# Lab7-8_TOP.net
KiCad netlist of a schematic drawn in Altium Designer
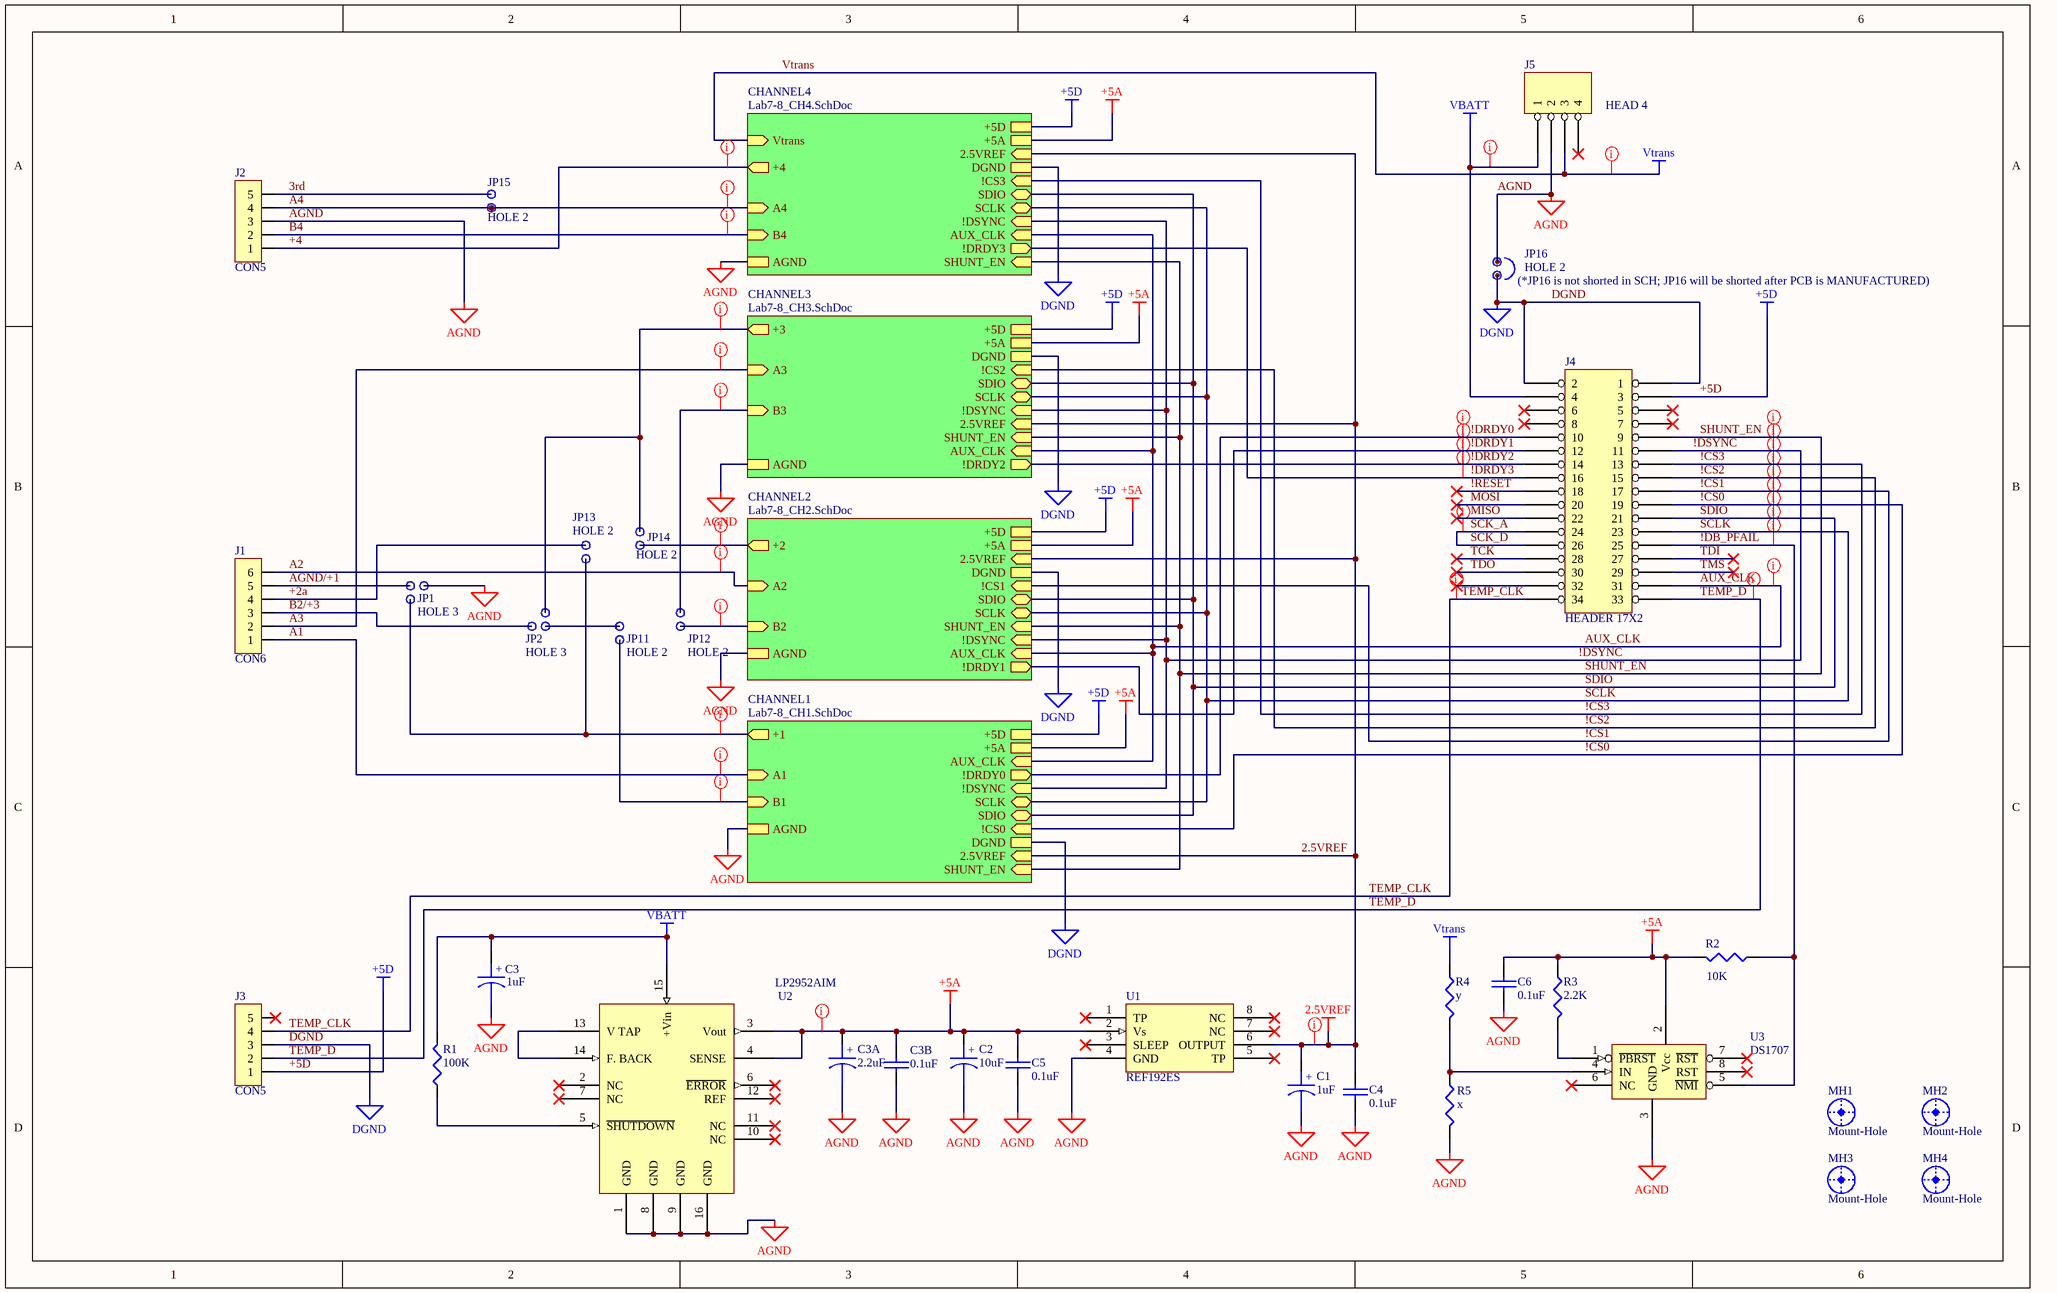
[diagram p0: Lab7-8_TOP.SchDoc]

(export (version "E")
  (design (tool "Eeschema 10.0.6"))
  (components
    (comp (ref "C1")
      (value "1uF")
      (footprint "3528")
      (libsource (lib "ECET231_ProjectThree_SCHLIB_Rev02") (part "CAPACITOR POL"))
    )
    (comp (ref "C2")
      (value "10uF")
      (footprint "3528")
      (libsource (lib "ECET231_ProjectThree_SCHLIB_Rev02") (part "CAPACITOR POL"))
    )
    (comp (ref "C3")
      (value "1uF")
      (footprint "3528")
      (libsource (lib "ECET231_ProjectThree_SCHLIB_Rev02") (part "CAPACITOR POL"))
    )
    (comp (ref "C3A")
      (value "2.2uF")
      (footprint "3528")
      (libsource (lib "ECET231_ProjectThree_SCHLIB_Rev02") (part "CAPACITOR POL"))
    )
    (comp (ref "C3B")
      (value "0.1uF")
      (footprint "0805")
      (libsource (lib "ECET231_ProjectThree_SCHLIB_Rev02") (part "CAP"))
    )
    (comp (ref "C4")
      (value "0.1uF")
      (footprint "0805")
      (libsource (lib "ECET231_ProjectThree_SCHLIB_Rev02") (part "CAP"))
    )
    (comp (ref "C5")
      (value "0.1uF")
      (footprint "0805")
      (libsource (lib "ECET231_ProjectThree_SCHLIB_Rev02") (part "CAP"))
    )
    (comp (ref "C6")
      (value "0.1uF")
      (footprint "0805")
      (libsource (lib "ECET231_ProjectThree_SCHLIB_Rev02") (part "CAP"))
    )
    (comp (ref "J1")
      (value "CON6")
      (footprint "FSFD4.6")
      (libsource (lib "ECET231_ProjectThree_SCHLIB_Rev02") (part "CON6"))
    )
    (comp (ref "J2")
      (value "CON5")
      (footprint "FSFD4.5")
      (libsource (lib "ECET231_ProjectThree_SCHLIB_Rev02") (part "CON5"))
    )
    (comp (ref "J3")
      (value "CON5")
      (footprint "FSFD4.5")
      (libsource (lib "ECET231_ProjectThree_SCHLIB_Rev02") (part "CON5"))
    )
    (comp (ref "J4")
      (value "HEADER 17X2")
      (footprint "HDR2X17")
      (libsource (lib "ECET231_ProjectThree_SCHLIB_Rev02") (part "HEADER 2X17"))
    )
    (comp (ref "J5")
      (value "HEAD 4")
      (footprint "70543-4A")
      (libsource (lib "ECET231_ProjectThree_SCHLIB_Rev02") (part "HEADER 4"))
    )
    (comp (ref "JP1")
      (value "HOLE 3")
      (footprint "RAD0.1A")
      (libsource (lib "ECET231_ProjectThree_SCHLIB_Rev02") (part "HOLE 3"))
    )
    (comp (ref "JP2")
      (value "HOLE 3")
      (footprint "RAD0.1A")
      (libsource (lib "ECET231_ProjectThree_SCHLIB_Rev02") (part "HOLE 3"))
    )
    (comp (ref "JP11")
      (value "HOLE 2")
      (footprint "RAD0.1")
      (libsource (lib "ECET231_ProjectThree_SCHLIB_Rev02") (part "HOLE 2"))
    )
    (comp (ref "JP12")
      (value "HOLE 2")
      (footprint "RAD0.1")
      (libsource (lib "ECET231_ProjectThree_SCHLIB_Rev02") (part "HOLE 2"))
    )
    (comp (ref "JP13")
      (value "HOLE 2")
      (footprint "RAD0.1")
      (libsource (lib "ECET231_ProjectThree_SCHLIB_Rev02") (part "HOLE 2"))
    )
    (comp (ref "JP14")
      (value "HOLE 2")
      (footprint "RAD0.1")
      (libsource (lib "ECET231_ProjectThree_SCHLIB_Rev02") (part "HOLE 2"))
    )
    (comp (ref "JP15")
      (value "HOLE 2")
      (footprint "RAD0.1")
      (libsource (lib "ECET231_ProjectThree_SCHLIB_Rev02") (part "HOLE 2"))
    )
    (comp (ref "JP16")
      (value "HOLE 2")
      (footprint "RAD0.1")
      (libsource (lib "ECET231_ProjectThree_SCHLIB_Rev02") (part "HOLE 2"))
    )
    (comp (ref "MH1")
      (value "Mount-Hole")
      (footprint "screw 4-40")
      (description "Mount hole")
      (fields (field (name "PUBLISHER") "Altium Limited"))
      (libsource (lib "ECET231_ProjectThree_SCHLIB_Rev02") (part "MountHole"))
    )
    (comp (ref "MH2")
      (value "Mount-Hole")
      (footprint "screw 4-40")
      (description "Mount hole")
      (fields (field (name "PUBLISHER") "Altium Limited"))
      (libsource (lib "ECET231_ProjectThree_SCHLIB_Rev02") (part "MountHole"))
    )
    (comp (ref "MH3")
      (value "Mount-Hole")
      (footprint "screw 4-40")
      (description "Mount hole")
      (fields (field (name "PUBLISHER") "Altium Limited"))
      (libsource (lib "ECET231_ProjectThree_SCHLIB_Rev02") (part "MountHole"))
    )
    (comp (ref "MH4")
      (value "Mount-Hole")
      (footprint "screw 4-40")
      (description "Mount hole")
      (fields (field (name "PUBLISHER") "Altium Limited"))
      (libsource (lib "ECET231_ProjectThree_SCHLIB_Rev02") (part "MountHole"))
    )
    (comp (ref "R1")
      (value "100K")
      (footprint "0805")
      (libsource (lib "ECET231_ProjectThree_SCHLIB_Rev02") (part "RES1"))
    )
    (comp (ref "R2")
      (value "10K")
      (footprint "0805")
      (libsource (lib "ECET231_ProjectThree_SCHLIB_Rev02") (part "RES1"))
    )
    (comp (ref "R3")
      (value "2.2K")
      (footprint "0805")
      (libsource (lib "ECET231_ProjectThree_SCHLIB_Rev02") (part "RES1"))
    )
    (comp (ref "R4")
      (value "y")
      (footprint "0805")
      (libsource (lib "ECET231_ProjectThree_SCHLIB_Rev02") (part "RES1"))
    )
    (comp (ref "R5")
      (value "x")
      (footprint "0805")
      (libsource (lib "ECET231_ProjectThree_SCHLIB_Rev02") (part "RES1"))
    )
    (comp (ref "U1")
      (value "REF192ES")
      (footprint "SO-8")
      (libsource (lib "ECET231_ProjectThree_SCHLIB_Rev02") (part "REF192ES"))
    )
    (comp (ref "U2")
      (value "LP2952AIM")
      (footprint "SO-16")
      (libsource (lib "ECET231_ProjectThree_SCHLIB_Rev02") (part "LP2952AIM"))
    )
    (comp (ref "U3")
      (value "DS1707")
      (footprint "SO-8")
      (libsource (lib "ECET231_ProjectThree_SCHLIB_Rev02") (part "DS1707"))
    )
  )
  (nets
    (net (code "1") (name "+5A") (class "Default")
      (node (ref "C2") (pin "1") (pinfunction "1_1") (pintype "passive"))
      (node (ref "C3A") (pin "1") (pinfunction "1_1") (pintype "passive"))
      (node (ref "C3B") (pin "1") (pintype "passive"))
      (node (ref "C5") (pin "1") (pintype "passive"))
      (node (ref "C6") (pin "1") (pintype "passive"))
      (node (ref "R2") (pin "2") (pintype "passive"))
      (node (ref "R3") (pin "1") (pintype "passive"))
      (node (ref "U1") (pin "2") (pinfunction "Vs_2") (pintype "input"))
      (node (ref "U2") (pin "3") (pinfunction "Vout_3") (pintype "output"))
      (node (ref "U2") (pin "4") (pinfunction "SENSE_4") (pintype "passive"))
      (node (ref "U3") (pin "2") (pinfunction "Vcc_2") (pintype "power_in"))
    )
    (net (code "2") (name "+5D") (class "Default")
      (node (ref "J3") (pin "1") (pinfunction "1_1") (pintype "passive"))
      (node (ref "J4") (pin "3") (pinfunction "3_3") (pintype "passive"))
    )
    (net (code "3") (name "/!CS0") (class "Default")
      (node (ref "J4") (pin "19") (pinfunction "19_19") (pintype "passive"))
    )
    (net (code "4") (name "/!CS1") (class "Default")
      (node (ref "J4") (pin "17") (pinfunction "17_17") (pintype "passive"))
    )
    (net (code "5") (name "/!CS2") (class "Default")
      (node (ref "J4") (pin "15") (pinfunction "15_15") (pintype "passive"))
    )
    (net (code "6") (name "/!CS3") (class "Default")
      (node (ref "J4") (pin "13") (pinfunction "13_13") (pintype "passive"))
    )
    (net (code "7") (name "/!DB_PFAIL") (class "Default")
      (node (ref "J4") (pin "25") (pinfunction "25_25") (pintype "passive"))
      (node (ref "R2") (pin "1") (pintype "passive"))
      (node (ref "U3") (pin "5") (pinfunction "~{NMI}_5") (pintype "passive"))
    )
    (net (code "8") (name "/!DRDY0") (class "Default")
      (node (ref "J4") (pin "10") (pinfunction "10_10") (pintype "passive"))
    )
    (net (code "9") (name "/!DRDY1") (class "Default")
      (node (ref "J4") (pin "12") (pinfunction "12_12") (pintype "passive"))
    )
    (net (code "10") (name "/!DRDY2") (class "Default")
      (node (ref "J4") (pin "14") (pinfunction "14_14") (pintype "passive"))
    )
    (net (code "11") (name "/!DRDY3") (class "Default")
      (node (ref "J4") (pin "16") (pinfunction "16_16") (pintype "passive"))
    )
    (net (code "12") (name "/!DSYNC") (class "Default")
      (node (ref "J4") (pin "11") (pinfunction "11_11") (pintype "passive"))
    )
    (net (code "13") (name "/!RESET") (class "Default")
      (node (ref "J4") (pin "18") (pinfunction "18_18") (pintype "passive+no_connect"))
    )
    (net (code "14") (name "/+1") (class "Default")
      (node (ref "JP1") (pin "1") (pinfunction "1_1") (pintype "passive"))
      (node (ref "JP13") (pin "1") (pinfunction "1_1") (pintype "passive"))
    )
    (net (code "15") (name "/+2") (class "Default")
      (node (ref "JP14") (pin "1") (pinfunction "1_1") (pintype "passive"))
    )
    (net (code "16") (name "/+2a") (class "Default")
      (node (ref "J1") (pin "4") (pinfunction "4_4") (pintype "passive"))
      (node (ref "JP13") (pin "2") (pinfunction "2_2") (pintype "passive"))
    )
    (net (code "17") (name "/+3") (class "Default")
      (node (ref "JP14") (pin "2") (pinfunction "2_2") (pintype "passive"))
      (node (ref "JP2") (pin "1") (pinfunction "1_1") (pintype "passive"))
    )
    (net (code "18") (name "/+4") (class "Default")
      (node (ref "J2") (pin "1") (pinfunction "1_1") (pintype "passive"))
    )
    (net (code "19") (name "/3rd") (class "Default")
      (node (ref "J2") (pin "5") (pinfunction "5_5") (pintype "passive"))
      (node (ref "JP15") (pin "2") (pinfunction "2_2") (pintype "passive"))
    )
    (net (code "20") (name "/A1") (class "Default")
      (node (ref "J1") (pin "1") (pinfunction "1_1") (pintype "passive"))
    )
    (net (code "21") (name "/A2") (class "Default")
      (node (ref "J1") (pin "6") (pinfunction "6_6") (pintype "passive"))
    )
    (net (code "22") (name "/A3") (class "Default")
      (node (ref "J1") (pin "2") (pinfunction "2_2") (pintype "passive"))
    )
    (net (code "23") (name "/A4") (class "Default")
      (node (ref "J2") (pin "4") (pinfunction "4_4") (pintype "passive"))
      (node (ref "JP15") (pin "1") (pinfunction "1_1") (pintype "passive"))
    )
    (net (code "24") (name "/AGND{slash}+1") (class "Default")
      (node (ref "J1") (pin "5") (pinfunction "5_5") (pintype "passive"))
      (node (ref "JP1") (pin "2") (pinfunction "2_2") (pintype "passive"))
    )
    (net (code "25") (name "/AUX_CLK") (class "Default")
      (node (ref "J4") (pin "31") (pinfunction "31_31") (pintype "passive"))
    )
    (net (code "26") (name "/B1") (class "Default")
      (node (ref "JP11") (pin "1") (pinfunction "1_1") (pintype "passive"))
    )
    (net (code "27") (name "/B2") (class "Default")
      (node (ref "JP12") (pin "1") (pinfunction "1_1") (pintype "passive"))
    )
    (net (code "28") (name "/B2{slash}+3") (class "Default")
      (node (ref "J1") (pin "3") (pinfunction "3_3") (pintype "passive"))
      (node (ref "JP2") (pin "3") (pinfunction "3_3") (pintype "passive"))
    )
    (net (code "29") (name "/B3") (class "Default")
      (node (ref "JP12") (pin "2") (pinfunction "2_2") (pintype "passive"))
    )
    (net (code "30") (name "/B4") (class "Default")
      (node (ref "J2") (pin "2") (pinfunction "2_2") (pintype "passive"))
    )
    (net (code "31") (name "/MISO") (class "Default")
      (node (ref "J4") (pin "22") (pinfunction "22_22") (pintype "passive+no_connect"))
    )
    (net (code "32") (name "/MOSI") (class "Default")
      (node (ref "J4") (pin "20") (pinfunction "20_20") (pintype "passive+no_connect"))
    )
    (net (code "33") (name "/SCK_A") (class "Default")
      (node (ref "J4") (pin "24") (pinfunction "24_24") (pintype "passive"))
      (node (ref "J4") (pin "26") (pinfunction "26_26") (pintype "passive"))
    )
    (net (code "34") (name "/SCLK") (class "Default")
      (node (ref "J4") (pin "23") (pinfunction "23_23") (pintype "passive"))
    )
    (net (code "35") (name "/SDIO") (class "Default")
      (node (ref "J4") (pin "21") (pinfunction "21_21") (pintype "passive"))
    )
    (net (code "36") (name "/SHUNT_EN") (class "Default")
      (node (ref "J4") (pin "9") (pinfunction "9_9") (pintype "passive"))
    )
    (net (code "37") (name "/TCK") (class "Default")
      (node (ref "J4") (pin "28") (pinfunction "28_28") (pintype "passive+no_connect"))
    )
    (net (code "38") (name "/TDI") (class "Default")
      (node (ref "J4") (pin "27") (pinfunction "27_27") (pintype "passive+no_connect"))
    )
    (net (code "39") (name "/TDO") (class "Default")
      (node (ref "J4") (pin "30") (pinfunction "30_30") (pintype "passive+no_connect"))
    )
    (net (code "40") (name "/TEMP_CLK") (class "Default")
      (node (ref "J3") (pin "4") (pinfunction "4_4") (pintype "passive"))
      (node (ref "J4") (pin "34") (pinfunction "34_34") (pintype "passive"))
    )
    (net (code "41") (name "/TEMP_D") (class "Default")
      (node (ref "J3") (pin "2") (pinfunction "2_2") (pintype "passive"))
      (node (ref "J4") (pin "33") (pinfunction "33_33") (pintype "passive"))
    )
    (net (code "42") (name "/TMS") (class "Default")
      (node (ref "J4") (pin "29") (pinfunction "29_29") (pintype "passive+no_connect"))
    )
    (net (code "43") (name "2.5VREF") (class "Default")
      (node (ref "C1") (pin "1") (pinfunction "1_1") (pintype "passive"))
      (node (ref "C4") (pin "1") (pintype "passive"))
      (node (ref "U1") (pin "6") (pinfunction "OUTPUT_6") (pintype "passive"))
    )
    (net (code "44") (name "AGND") (class "Default")
      (node (ref "C1") (pin "2") (pinfunction "2_2") (pintype "passive"))
      (node (ref "C2") (pin "2") (pinfunction "2_2") (pintype "passive"))
      (node (ref "C3") (pin "2") (pinfunction "2_2") (pintype "passive"))
      (node (ref "C3A") (pin "2") (pinfunction "2_2") (pintype "passive"))
      (node (ref "C3B") (pin "2") (pintype "passive"))
      (node (ref "C4") (pin "2") (pintype "passive"))
      (node (ref "C5") (pin "2") (pintype "passive"))
      (node (ref "C6") (pin "2") (pintype "passive"))
      (node (ref "J2") (pin "3") (pinfunction "3_3") (pintype "passive"))
      (node (ref "J5") (pin "2") (pinfunction "2_2") (pintype "passive"))
      (node (ref "JP1") (pin "3") (pinfunction "3_3") (pintype "passive"))
      (node (ref "JP16") (pin "2") (pinfunction "2_2") (pintype "passive"))
      (node (ref "R5") (pin "2") (pintype "passive"))
      (node (ref "U1") (pin "4") (pinfunction "GND_4") (pintype "passive"))
      (node (ref "U2") (pin "1") (pinfunction "GND_1") (pintype "passive"))
      (node (ref "U2") (pin "16") (pinfunction "GND_16") (pintype "passive"))
      (node (ref "U2") (pin "8") (pinfunction "GND_8") (pintype "passive"))
      (node (ref "U2") (pin "9") (pinfunction "GND_9") (pintype "passive"))
      (node (ref "U3") (pin "3") (pinfunction "GND_3") (pintype "passive"))
    )
    (net (code "45") (name "DGND") (class "Default")
      (node (ref "J3") (pin "3") (pinfunction "3_3") (pintype "passive"))
      (node (ref "J4") (pin "1") (pinfunction "1_1") (pintype "passive"))
      (node (ref "J4") (pin "2") (pinfunction "2_2") (pintype "passive"))
      (node (ref "JP16") (pin "1") (pinfunction "1_1") (pintype "passive"))
    )
    (net (code "46") (name "Net-(JP11-Pad2)") (class "Default")
      (node (ref "JP11") (pin "2") (pinfunction "2_2") (pintype "passive"))
      (node (ref "JP2") (pin "2") (pinfunction "2_2") (pintype "passive"))
    )
    (net (code "47") (name "Net-(U2-F._BACK)") (class "Default")
      (node (ref "U2") (pin "13") (pinfunction "V_TAP_13") (pintype "passive"))
      (node (ref "U2") (pin "14") (pinfunction "F._BACK_14") (pintype "input"))
    )
    (net (code "48") (name "Net-(U2-~{SHUTDOWN})") (class "Default")
      (node (ref "R1") (pin "1") (pintype "passive"))
      (node (ref "U2") (pin "5") (pinfunction "~{SHUTDOWN}_5") (pintype "input"))
    )
    (net (code "49") (name "Net-(U3-IN)") (class "Default")
      (node (ref "R4") (pin "2") (pintype "passive"))
      (node (ref "R5") (pin "1") (pintype "passive"))
      (node (ref "U3") (pin "4") (pinfunction "IN_4") (pintype "input"))
    )
    (net (code "50") (name "Net-(U3-~{PBRST})") (class "Default")
      (node (ref "R3") (pin "2") (pintype "passive"))
      (node (ref "U3") (pin "1") (pinfunction "~{PBRST}_1") (pintype "input"))
    )
    (net (code "51") (name "VBATT") (class "Default")
      (node (ref "C3") (pin "1") (pinfunction "1_1") (pintype "passive"))
      (node (ref "J4") (pin "4") (pinfunction "4_4") (pintype "passive"))
      (node (ref "J5") (pin "1") (pinfunction "1_1") (pintype "passive"))
      (node (ref "R1") (pin "2") (pintype "passive"))
      (node (ref "U2") (pin "15") (pinfunction "+Vin_15") (pintype "input"))
    )
    (net (code "52") (name "Vtrans") (class "Default")
      (node (ref "J5") (pin "3") (pinfunction "3_3") (pintype "passive"))
      (node (ref "R4") (pin "1") (pintype "passive"))
    )
    (net (code "53") (name "unconnected-(J3-Pad5)") (class "Default")
      (node (ref "J3") (pin "5") (pinfunction "5_5") (pintype "passive+no_connect"))
    )
    (net (code "54") (name "unconnected-(J4-Pad5)") (class "Default")
      (node (ref "J4") (pin "5") (pinfunction "5_5") (pintype "passive+no_connect"))
    )
    (net (code "55") (name "unconnected-(J4-Pad6)") (class "Default")
      (node (ref "J4") (pin "6") (pinfunction "6_6") (pintype "passive+no_connect"))
    )
    (net (code "56") (name "unconnected-(J4-Pad7)") (class "Default")
      (node (ref "J4") (pin "7") (pinfunction "7_7") (pintype "passive+no_connect"))
    )
    (net (code "57") (name "unconnected-(J4-Pad8)") (class "Default")
      (node (ref "J4") (pin "8") (pinfunction "8_8") (pintype "passive+no_connect"))
    )
    (net (code "58") (name "unconnected-(J4-Pad32)") (class "Default")
      (node (ref "J4") (pin "32") (pinfunction "32_32") (pintype "passive+no_connect"))
    )
    (net (code "59") (name "unconnected-(J5-Pad4)") (class "Default")
      (node (ref "J5") (pin "4") (pinfunction "4_4") (pintype "passive+no_connect"))
    )
    (net (code "60") (name "unconnected-(U1-NC-Pad7)") (class "Default")
      (node (ref "U1") (pin "7") (pinfunction "NC_7") (pintype "passive+no_connect"))
    )
    (net (code "61") (name "unconnected-(U1-NC-Pad8)") (class "Default")
      (node (ref "U1") (pin "8") (pinfunction "NC_8") (pintype "passive+no_connect"))
    )
    (net (code "62") (name "unconnected-(U1-SLEEP-Pad3)") (class "Default")
      (node (ref "U1") (pin "3") (pinfunction "SLEEP_3") (pintype "passive+no_connect"))
    )
    (net (code "63") (name "unconnected-(U1-TP-Pad1)") (class "Default")
      (node (ref "U1") (pin "1") (pinfunction "TP_1") (pintype "passive+no_connect"))
    )
    (net (code "64") (name "unconnected-(U1-TP-Pad5)") (class "Default")
      (node (ref "U1") (pin "5") (pinfunction "TP_5") (pintype "passive+no_connect"))
    )
    (net (code "65") (name "unconnected-(U2-NC-Pad2)") (class "Default")
      (node (ref "U2") (pin "2") (pinfunction "NC_2") (pintype "passive+no_connect"))
    )
    (net (code "66") (name "unconnected-(U2-NC-Pad7)") (class "Default")
      (node (ref "U2") (pin "7") (pinfunction "NC_7") (pintype "passive+no_connect"))
    )
    (net (code "67") (name "unconnected-(U2-NC-Pad10)") (class "Default")
      (node (ref "U2") (pin "10") (pinfunction "NC_10") (pintype "passive+no_connect"))
    )
    (net (code "68") (name "unconnected-(U2-NC-Pad11)") (class "Default")
      (node (ref "U2") (pin "11") (pinfunction "NC_11") (pintype "passive+no_connect"))
    )
    (net (code "69") (name "unconnected-(U2-REF-Pad12)") (class "Default")
      (node (ref "U2") (pin "12") (pinfunction "REF_12") (pintype "passive+no_connect"))
    )
    (net (code "70") (name "unconnected-(U2-~{ERROR}-Pad6)") (class "Default")
      (node (ref "U2") (pin "6") (pinfunction "~{ERROR}_6") (pintype "output+no_connect"))
    )
    (net (code "71") (name "unconnected-(U3-NC-Pad6)") (class "Default")
      (node (ref "U3") (pin "6") (pinfunction "NC_6") (pintype "passive+no_connect"))
    )
    (net (code "72") (name "unconnected-(U3-RST-Pad8)") (class "Default")
      (node (ref "U3") (pin "8") (pinfunction "RST_8") (pintype "passive+no_connect"))
    )
    (net (code "73") (name "unconnected-(U3-~{RST}-Pad7)") (class "Default")
      (node (ref "U3") (pin "7") (pinfunction "~{RST}_7") (pintype "passive+no_connect"))
    )
  )
)
